# power.net
KiCad netlist of a schematic drawn in Altium Designer
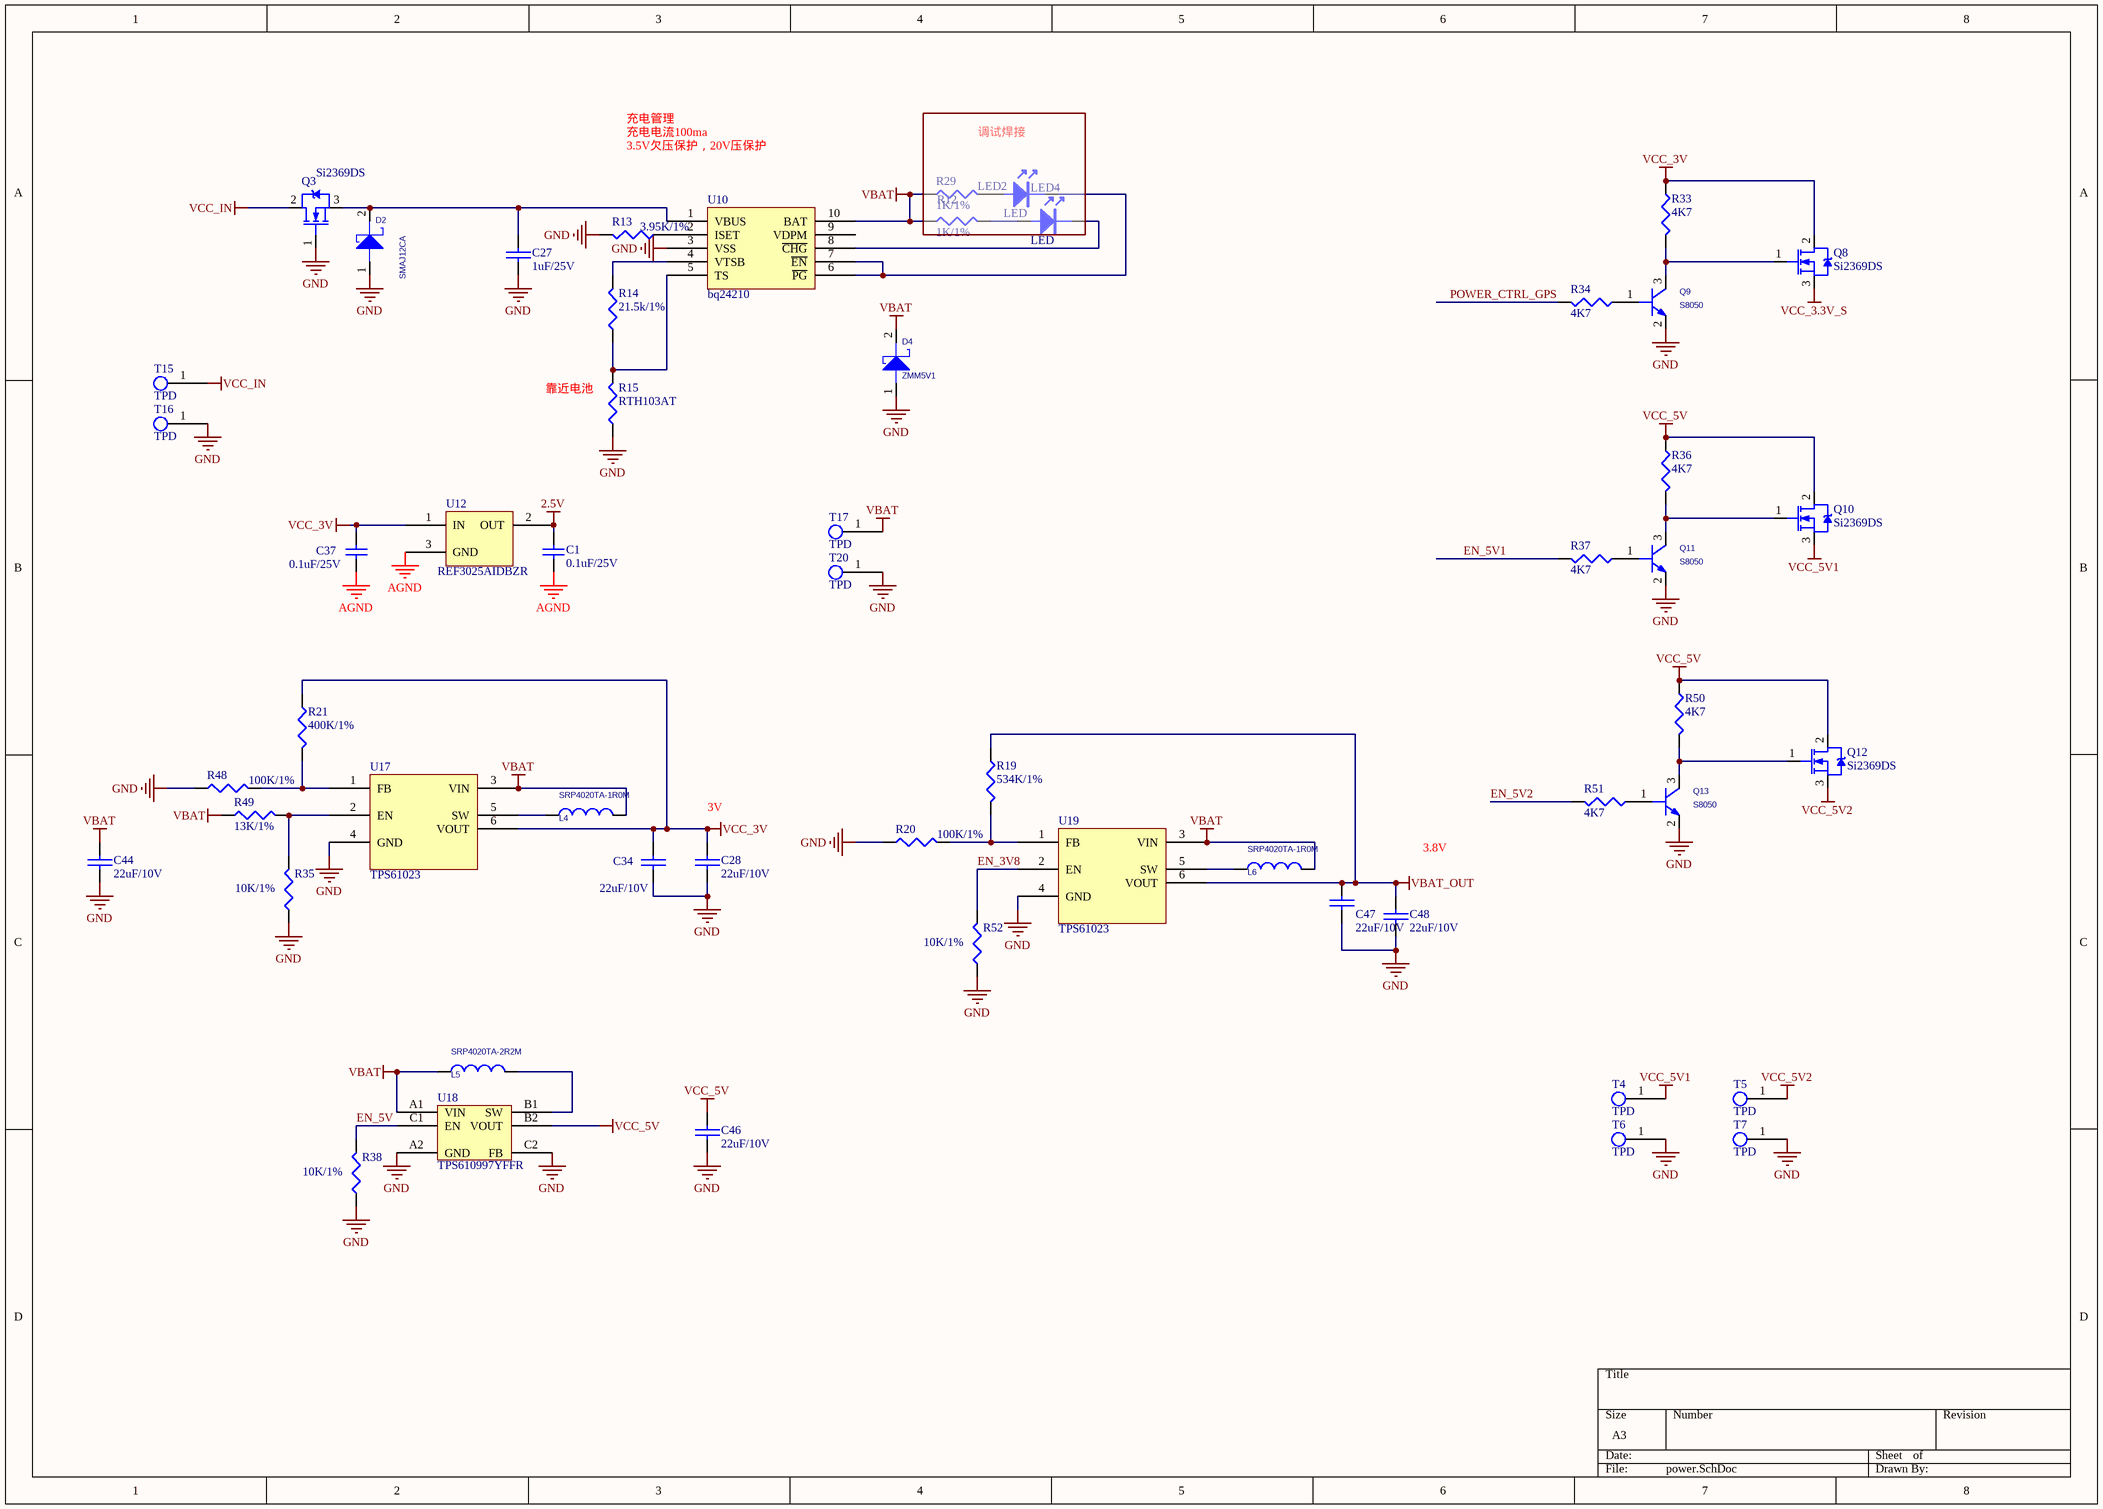
[diagram p0: power.SchDoc]

(export (version "E")
  (design (tool "Eeschema 10.0.6"))
  (components
    (comp (ref "C1")
      (value "0.1uF/25V")
      (footprint "0402c")
      (description "Capacitor")
      (fields (field (name "PUBLISHER") "Altium Limited"))
      (libsource (lib "Miscellaneous Devices") (part "Cap"))
    )
    (comp (ref "C27")
      (value "1uF/25V")
      (footprint "0402C")
      (description "Capacitor")
      (libsource (lib "ZWLIntegrated_Library") (part "CAP"))
    )
    (comp (ref "C28")
      (value "22uF/10V")
      (footprint "0805C")
      (description "Capacitor")
      (libsource (lib "ZWLIntegrated_Library") (part "CAP"))
    )
    (comp (ref "C34")
      (value "22uF/10V")
      (footprint "0805C")
      (description "Capacitor")
      (libsource (lib "ZWLIntegrated_Library") (part "CAP"))
    )
    (comp (ref "C37")
      (value "0.1uF/25V")
      (footprint "0402c")
      (description "Capacitor")
      (fields (field (name "PUBLISHER") "Altium Limited"))
      (libsource (lib "Miscellaneous Devices") (part "Cap"))
    )
    (comp (ref "C44")
      (value "22uF/10V")
      (footprint "0805C")
      (description "Capacitor")
      (libsource (lib "ZWLIntegrated_Library") (part "CAP"))
    )
    (comp (ref "C46")
      (value "22uF/10V")
      (footprint "0805C")
      (description "Capacitor")
      (libsource (lib "ZWLIntegrated_Library") (part "CAP"))
    )
    (comp (ref "C47")
      (value "22uF/10V")
      (footprint "0805C")
      (description "Capacitor")
      (libsource (lib "ZWLIntegrated_Library") (part "CAP"))
    )
    (comp (ref "C48")
      (value "22uF/10V")
      (footprint "0805C")
      (description "Capacitor")
      (libsource (lib "ZWLIntegrated_Library") (part "CAP"))
    )
    (comp (ref "D2")
      (value "SMAJ12CA")
      (footprint "SMA")
      (libsource (lib "KT_iBeacon") (part "DIODE_SCHOTTKY_0"))
    )
    (comp (ref "D4")
      (value "ZMM5V1")
      (footprint "LL-34(D1206)")
      (fields (field (name "Comment") "DIODE_SCHOTTKY_0"))
      (libsource (lib "KT_iBeacon") (part "DIODE_SCHOTTKY_0"))
    )
    (comp (ref "L4") (value "SRP4020TA-1R0M") (footprint "L2520") (libsource (lib "*") (part "INDUCTOR_1")))
    (comp (ref "L5") (value "SRP4020TA-2R2M") (footprint "L2520") (libsource (lib "*") (part "INDUCTOR_1")))
    (comp (ref "L6") (value "SRP4020TA-1R0M") (footprint "L2520") (libsource (lib "*") (part "INDUCTOR_1")))
    (comp (ref "LED2") (value "LED") (footprint "0603LED") (libsource (lib "我的元件库") (part "LED")))
    (comp (ref "LED4") (value "LED") (footprint "0603LED") (libsource (lib "我的元件库") (part "LED")))
    (comp (ref "Q3")
      (value "Si2369DS")
      (footprint "sot23-3")
      (description "NMOSFET")
      (libsource (lib "SM") (part "NCE4060K"))
    )
    (comp (ref "Q8")
      (value "Si2369DS")
      (footprint "sot23-3")
      (description "NMOSFET")
      (libsource (lib "SM") (part "NCE4060K"))
    )
    (comp (ref "Q9") (value "S8050") (footprint "SOT23-3") (libsource (lib "*") (part "2N1069_1")))
    (comp (ref "Q10")
      (value "Si2369DS")
      (footprint "sot23-3")
      (description "NMOSFET")
      (libsource (lib "SM") (part "NCE4060K"))
    )
    (comp (ref "Q11") (value "S8050") (footprint "SOT23-3") (libsource (lib "*") (part "2N1069_1")))
    (comp (ref "Q12")
      (value "Si2369DS")
      (footprint "sot23-3")
      (description "NMOSFET")
      (libsource (lib "SM") (part "NCE4060K"))
    )
    (comp (ref "Q13") (value "S8050") (footprint "SOT23-3") (libsource (lib "*") (part "2N1069_1")))
    (comp (ref "R12")
      (value "1K/1%")
      (footprint "0402R")
      (libsource (lib "ZWLIntegrated_Library") (part "RES1"))
    )
    (comp (ref "R13")
      (value "3.95K/1%")
      (footprint "0402R")
      (libsource (lib "ZWLIntegrated_Library") (part "RES1"))
    )
    (comp (ref "R14")
      (value "21.5k/1%")
      (footprint "0402R")
      (libsource (lib "ZWLIntegrated_Library") (part "RES1"))
    )
    (comp (ref "R15")
      (value "RTH103AT")
      (footprint "0603R")
      (libsource (lib "ZWLIntegrated_Library") (part "RES1"))
    )
    (comp (ref "R19")
      (value "534K/1%")
      (footprint "0402R")
      (libsource (lib "ZWLIntegrated_Library") (part "RES1"))
    )
    (comp (ref "R20")
      (value "100K/1%")
      (footprint "0402R")
      (libsource (lib "ZWLIntegrated_Library") (part "RES1"))
    )
    (comp (ref "R21")
      (value "400K/1%")
      (footprint "0402R")
      (libsource (lib "ZWLIntegrated_Library") (part "RES1"))
    )
    (comp (ref "R29")
      (value "1K/1%")
      (footprint "0402R")
      (libsource (lib "ZWLIntegrated_Library") (part "RES1"))
    )
    (comp (ref "R33")
      (value "4K7")
      (footprint "0402R")
      (libsource (lib "ZWLIntegrated_Library") (part "RES1"))
    )
    (comp (ref "R34")
      (value "4K7")
      (footprint "0402R")
      (libsource (lib "ZWLIntegrated_Library") (part "RES1"))
    )
    (comp (ref "R35")
      (value "10K/1%")
      (footprint "0402R")
      (libsource (lib "ZWLIntegrated_Library") (part "RES1"))
    )
    (comp (ref "R36")
      (value "4K7")
      (footprint "0402R")
      (libsource (lib "ZWLIntegrated_Library") (part "RES1"))
    )
    (comp (ref "R37")
      (value "4K7")
      (footprint "0402R")
      (libsource (lib "ZWLIntegrated_Library") (part "RES1"))
    )
    (comp (ref "R38")
      (value "10K/1%")
      (footprint "0402R")
      (libsource (lib "ZWLIntegrated_Library") (part "RES1"))
    )
    (comp (ref "R48")
      (value "100K/1%")
      (footprint "0402R")
      (libsource (lib "ZWLIntegrated_Library") (part "RES1"))
    )
    (comp (ref "R49")
      (value "13K/1%")
      (footprint "0402R")
      (libsource (lib "ZWLIntegrated_Library") (part "RES1"))
    )
    (comp (ref "R50")
      (value "4K7")
      (footprint "0402R")
      (libsource (lib "ZWLIntegrated_Library") (part "RES1"))
    )
    (comp (ref "R51")
      (value "4K7")
      (footprint "0402R")
      (libsource (lib "ZWLIntegrated_Library") (part "RES1"))
    )
    (comp (ref "R52")
      (value "10K/1%")
      (footprint "0402R")
      (libsource (lib "ZWLIntegrated_Library") (part "RES1"))
    )
    (comp (ref "T4") (value "TPD") (footprint "Pcblib_20110825:TP") (libsource (lib "stm32") (part "TPD")))
    (comp (ref "T5") (value "TPD") (footprint "Pcblib_20110825:TP") (libsource (lib "stm32") (part "TPD")))
    (comp (ref "T6") (value "TPD") (footprint "Pcblib_20110825:TP") (libsource (lib "stm32") (part "TPD")))
    (comp (ref "T7") (value "TPD") (footprint "Pcblib_20110825:TP") (libsource (lib "stm32") (part "TPD")))
    (comp (ref "T15") (value "TPD") (footprint "Pcblib_20110825:TP") (libsource (lib "stm32") (part "TPD")))
    (comp (ref "T16") (value "TPD") (footprint "Pcblib_20110825:TP") (libsource (lib "stm32") (part "TPD")))
    (comp (ref "T17") (value "TPD") (footprint "Pcblib_20110825:TP") (libsource (lib "stm32") (part "TPD")))
    (comp (ref "T20") (value "TPD") (footprint "Pcblib_20110825:TP") (libsource (lib "stm32") (part "TPD")))
    (comp (ref "U10")
      (value "bq24210")
      (footprint "QFN50P200X300X80-10N")
      (libsource (lib "stm32") (part "bq2410"))
    )
    (comp (ref "U12")
      (value "REF3025AIDBZR")
      (footprint "SOT23-3")
      (libsource (lib "Schlib1") (part "REF3012"))
    )
    (comp (ref "U17") (value "TPS61023") (footprint "SOT563-6") (libsource (lib "stm32") (part "TPS61023")))
    (comp (ref "U18")
      (value "TPS610997YFFR")
      (footprint "TPS610997YFFR")
      (libsource (lib "stm32") (part "TPS610997YFFR"))
    )
    (comp (ref "U19") (value "TPS61023") (footprint "SOT563-6") (libsource (lib "stm32") (part "TPS61023")))
  )
  (nets
    (net (code "1") (name "/EN_3V8") (class "Default")
      (node (ref "R52") (pin "2") (pinfunction "2_2") (pintype "passive"))
      (node (ref "U19") (pin "2") (pinfunction "EN_2") (pintype "passive"))
    )
    (net (code "2") (name "/EN_5V") (class "Default")
      (node (ref "R38") (pin "2") (pinfunction "2_2") (pintype "passive"))
      (node (ref "U18") (pin "C1") (pinfunction "EN_C1") (pintype "passive"))
    )
    (net (code "3") (name "/EN_5V1") (class "Default")
      (node (ref "R37") (pin "2") (pinfunction "2_2") (pintype "passive"))
    )
    (net (code "4") (name "/EN_5V2") (class "Default")
      (node (ref "R51") (pin "2") (pinfunction "2_2") (pintype "passive"))
    )
    (net (code "5") (name "/POWER_CTRL_GPS") (class "Default")
      (node (ref "R34") (pin "2") (pinfunction "2_2") (pintype "passive"))
    )
    (net (code "6") (name "2.5V") (class "Default")
      (node (ref "C1") (pin "1") (pinfunction "1_1") (pintype "passive"))
      (node (ref "U12") (pin "2") (pinfunction "OUT_2") (pintype "passive"))
    )
    (net (code "7") (name "AGND") (class "Default")
      (node (ref "C1") (pin "2") (pinfunction "2_2") (pintype "passive"))
      (node (ref "C37") (pin "2") (pinfunction "2_2") (pintype "passive"))
      (node (ref "U12") (pin "3") (pinfunction "GND_3") (pintype "passive"))
    )
    (net (code "8") (name "GND") (class "Default")
      (node (ref "C27") (pin "2") (pinfunction "2_2") (pintype "passive"))
      (node (ref "C28") (pin "2") (pinfunction "2_2") (pintype "passive"))
      (node (ref "C34") (pin "2") (pinfunction "2_2") (pintype "passive"))
      (node (ref "C44") (pin "2") (pinfunction "2_2") (pintype "passive"))
      (node (ref "C46") (pin "2") (pinfunction "2_2") (pintype "passive"))
      (node (ref "C47") (pin "2") (pinfunction "2_2") (pintype "passive"))
      (node (ref "C48") (pin "2") (pinfunction "2_2") (pintype "passive"))
      (node (ref "D2") (pin "1") (pinfunction "1_1") (pintype "passive"))
      (node (ref "D4") (pin "1") (pinfunction "1_1") (pintype "passive"))
      (node (ref "Q11") (pin "2") (pinfunction "E_2") (pintype "passive"))
      (node (ref "Q13") (pin "2") (pinfunction "E_2") (pintype "passive"))
      (node (ref "Q3") (pin "1") (pinfunction "G_1") (pintype "passive"))
      (node (ref "Q9") (pin "2") (pinfunction "E_2") (pintype "passive"))
      (node (ref "R13") (pin "2") (pinfunction "2_2") (pintype "passive"))
      (node (ref "R15") (pin "1") (pinfunction "1_1") (pintype "passive"))
      (node (ref "R20") (pin "1") (pinfunction "1_1") (pintype "passive"))
      (node (ref "R35") (pin "1") (pinfunction "1_1") (pintype "passive"))
      (node (ref "R38") (pin "1") (pinfunction "1_1") (pintype "passive"))
      (node (ref "R48") (pin "1") (pinfunction "1_1") (pintype "passive"))
      (node (ref "R52") (pin "1") (pinfunction "1_1") (pintype "passive"))
      (node (ref "T16") (pin "1") (pintype "passive"))
      (node (ref "T20") (pin "1") (pintype "passive"))
      (node (ref "T6") (pin "1") (pintype "passive"))
      (node (ref "T7") (pin "1") (pintype "passive"))
      (node (ref "U10") (pin "3") (pinfunction "VSS_3") (pintype "passive"))
      (node (ref "U17") (pin "4") (pinfunction "GND_4") (pintype "passive"))
      (node (ref "U18") (pin "A2") (pinfunction "GND_A2") (pintype "passive"))
      (node (ref "U18") (pin "C2") (pinfunction "FB_C2") (pintype "passive"))
      (node (ref "U19") (pin "4") (pinfunction "GND_4") (pintype "passive"))
    )
    (net (code "9") (name "Net-(LED2-Pad1)") (class "Default")
      (node (ref "LED2") (pin "1") (pinfunction "1_1") (pintype "passive"))
      (node (ref "R29") (pin "2") (pinfunction "2_2") (pintype "passive"))
    )
    (net (code "10") (name "Net-(LED4-Pad1)") (class "Default")
      (node (ref "LED4") (pin "1") (pinfunction "1_1") (pintype "passive"))
      (node (ref "R12") (pin "2") (pinfunction "2_2") (pintype "passive"))
    )
    (net (code "11") (name "Net-(Q3-S)") (class "Default")
      (node (ref "C27") (pin "1") (pinfunction "1_1") (pintype "passive"))
      (node (ref "D2") (pin "2") (pinfunction "2_2") (pintype "passive"))
      (node (ref "Q3") (pin "3") (pinfunction "S_3") (pintype "passive"))
      (node (ref "U10") (pin "1") (pinfunction "VBUS_1") (pintype "passive"))
    )
    (net (code "12") (name "Net-(Q8-G)") (class "Default")
      (node (ref "Q8") (pin "1") (pinfunction "G_1") (pintype "passive"))
      (node (ref "Q9") (pin "3") (pinfunction "C_3") (pintype "passive"))
      (node (ref "R33") (pin "2") (pinfunction "2_2") (pintype "passive"))
    )
    (net (code "13") (name "Net-(Q9-B)") (class "Default")
      (node (ref "Q9") (pin "1") (pinfunction "B_1") (pintype "passive"))
      (node (ref "R34") (pin "1") (pinfunction "1_1") (pintype "passive"))
    )
    (net (code "14") (name "Net-(Q10-G)") (class "Default")
      (node (ref "Q10") (pin "1") (pinfunction "G_1") (pintype "passive"))
      (node (ref "Q11") (pin "3") (pinfunction "C_3") (pintype "passive"))
      (node (ref "R36") (pin "2") (pinfunction "2_2") (pintype "passive"))
    )
    (net (code "15") (name "Net-(Q11-B)") (class "Default")
      (node (ref "Q11") (pin "1") (pinfunction "B_1") (pintype "passive"))
      (node (ref "R37") (pin "1") (pinfunction "1_1") (pintype "passive"))
    )
    (net (code "16") (name "Net-(Q12-G)") (class "Default")
      (node (ref "Q12") (pin "1") (pinfunction "G_1") (pintype "passive"))
      (node (ref "Q13") (pin "3") (pinfunction "C_3") (pintype "passive"))
      (node (ref "R50") (pin "2") (pinfunction "2_2") (pintype "passive"))
    )
    (net (code "17") (name "Net-(Q13-B)") (class "Default")
      (node (ref "Q13") (pin "1") (pinfunction "B_1") (pintype "passive"))
      (node (ref "R51") (pin "1") (pinfunction "1_1") (pintype "passive"))
    )
    (net (code "18") (name "Net-(U10-ISET)") (class "Default")
      (node (ref "R13") (pin "1") (pinfunction "1_1") (pintype "passive"))
      (node (ref "U10") (pin "2") (pinfunction "ISET_2") (pintype "passive"))
    )
    (net (code "19") (name "Net-(U10-TS)") (class "Default")
      (node (ref "R14") (pin "1") (pinfunction "1_1") (pintype "passive"))
      (node (ref "R15") (pin "2") (pinfunction "2_2") (pintype "passive"))
      (node (ref "U10") (pin "5") (pinfunction "TS_5") (pintype "passive"))
    )
    (net (code "20") (name "Net-(U10-VTSB)") (class "Default")
      (node (ref "R14") (pin "2") (pinfunction "2_2") (pintype "passive"))
      (node (ref "U10") (pin "4") (pinfunction "VTSB_4") (pintype "passive"))
    )
    (net (code "21") (name "Net-(U10-~{CHG})") (class "Default")
      (node (ref "LED4") (pin "2") (pinfunction "2_2") (pintype "passive"))
      (node (ref "U10") (pin "8") (pinfunction "~{CHG}_8") (pintype "passive"))
    )
    (net (code "22") (name "Net-(U10-~{EN})") (class "Default")
      (node (ref "LED2") (pin "2") (pinfunction "2_2") (pintype "passive"))
      (node (ref "U10") (pin "6") (pinfunction "~{PG}_6") (pintype "passive"))
      (node (ref "U10") (pin "7") (pinfunction "~{EN}_7") (pintype "passive"))
    )
    (net (code "23") (name "Net-(U17-EN)") (class "Default")
      (node (ref "R35") (pin "2") (pinfunction "2_2") (pintype "passive"))
      (node (ref "R49") (pin "2") (pinfunction "2_2") (pintype "passive"))
      (node (ref "U17") (pin "2") (pinfunction "EN_2") (pintype "passive"))
    )
    (net (code "24") (name "Net-(U17-FB)") (class "Default")
      (node (ref "R21") (pin "2") (pinfunction "2_2") (pintype "passive"))
      (node (ref "R48") (pin "2") (pinfunction "2_2") (pintype "passive"))
      (node (ref "U17") (pin "1") (pinfunction "FB_1") (pintype "passive"))
    )
    (net (code "25") (name "Net-(U17-SW)") (class "Default")
      (node (ref "L4") (pin "1") (pinfunction "1_1") (pintype "passive"))
      (node (ref "U17") (pin "5") (pinfunction "SW_5") (pintype "passive"))
    )
    (net (code "26") (name "Net-(U18-SW)") (class "Default")
      (node (ref "L5") (pin "2") (pinfunction "2_2") (pintype "passive"))
      (node (ref "U18") (pin "B1") (pinfunction "SW_B1") (pintype "passive"))
    )
    (net (code "27") (name "Net-(U19-FB)") (class "Default")
      (node (ref "R19") (pin "2") (pinfunction "2_2") (pintype "passive"))
      (node (ref "R20") (pin "2") (pinfunction "2_2") (pintype "passive"))
      (node (ref "U19") (pin "1") (pinfunction "FB_1") (pintype "passive"))
    )
    (net (code "28") (name "Net-(U19-SW)") (class "Default")
      (node (ref "L6") (pin "1") (pinfunction "1_1") (pintype "passive"))
      (node (ref "U19") (pin "5") (pinfunction "SW_5") (pintype "passive"))
    )
    (net (code "29") (name "VBAT") (class "Default")
      (node (ref "C44") (pin "1") (pinfunction "1_1") (pintype "passive"))
      (node (ref "D4") (pin "2") (pinfunction "2_2") (pintype "passive"))
      (node (ref "L4") (pin "2") (pinfunction "2_2") (pintype "passive"))
      (node (ref "L5") (pin "1") (pinfunction "1_1") (pintype "passive"))
      (node (ref "L6") (pin "2") (pinfunction "2_2") (pintype "passive"))
      (node (ref "R12") (pin "1") (pinfunction "1_1") (pintype "passive"))
      (node (ref "R29") (pin "1") (pinfunction "1_1") (pintype "passive"))
      (node (ref "R49") (pin "1") (pinfunction "1_1") (pintype "passive"))
      (node (ref "T17") (pin "1") (pintype "passive"))
      (node (ref "U10") (pin "10") (pinfunction "BAT_10") (pintype "passive"))
      (node (ref "U17") (pin "3") (pinfunction "VIN_3") (pintype "passive"))
      (node (ref "U18") (pin "A1") (pinfunction "VIN_A1") (pintype "passive"))
      (node (ref "U19") (pin "3") (pinfunction "VIN_3") (pintype "passive"))
    )
    (net (code "30") (name "VBAT_OUT") (class "Default")
      (node (ref "C47") (pin "1") (pinfunction "1_1") (pintype "passive"))
      (node (ref "C48") (pin "1") (pinfunction "1_1") (pintype "passive"))
      (node (ref "R19") (pin "1") (pinfunction "1_1") (pintype "passive"))
      (node (ref "U19") (pin "6") (pinfunction "VOUT_6") (pintype "passive"))
    )
    (net (code "31") (name "VCC_3.3V_S") (class "Default")
      (node (ref "Q8") (pin "3") (pinfunction "S_3") (pintype "passive"))
    )
    (net (code "32") (name "VCC_3V") (class "Default")
      (node (ref "C28") (pin "1") (pinfunction "1_1") (pintype "passive"))
      (node (ref "C34") (pin "1") (pinfunction "1_1") (pintype "passive"))
      (node (ref "C37") (pin "1") (pinfunction "1_1") (pintype "passive"))
      (node (ref "Q8") (pin "2") (pinfunction "D_2") (pintype "passive"))
      (node (ref "R21") (pin "1") (pinfunction "1_1") (pintype "passive"))
      (node (ref "R33") (pin "1") (pinfunction "1_1") (pintype "passive"))
      (node (ref "U12") (pin "1") (pinfunction "IN_1") (pintype "passive"))
      (node (ref "U17") (pin "6") (pinfunction "VOUT_6") (pintype "passive"))
    )
    (net (code "33") (name "VCC_5V") (class "Default")
      (node (ref "C46") (pin "1") (pinfunction "1_1") (pintype "passive"))
      (node (ref "Q10") (pin "2") (pinfunction "D_2") (pintype "passive"))
      (node (ref "Q12") (pin "2") (pinfunction "D_2") (pintype "passive"))
      (node (ref "R36") (pin "1") (pinfunction "1_1") (pintype "passive"))
      (node (ref "R50") (pin "1") (pinfunction "1_1") (pintype "passive"))
      (node (ref "U18") (pin "B2") (pinfunction "VOUT_B2") (pintype "passive"))
    )
    (net (code "34") (name "VCC_5V1") (class "Default")
      (node (ref "Q10") (pin "3") (pinfunction "S_3") (pintype "passive"))
      (node (ref "T4") (pin "1") (pintype "passive"))
    )
    (net (code "35") (name "VCC_5V2") (class "Default")
      (node (ref "Q12") (pin "3") (pinfunction "S_3") (pintype "passive"))
      (node (ref "T5") (pin "1") (pintype "passive"))
    )
    (net (code "36") (name "VCC_IN") (class "Default")
      (node (ref "Q3") (pin "2") (pinfunction "D_2") (pintype "passive"))
      (node (ref "T15") (pin "1") (pintype "passive"))
    )
    (net (code "37") (name "unconnected-(U10-VDPM-Pad9)") (class "Default")
      (node (ref "U10") (pin "9") (pinfunction "VDPM_9") (pintype "passive"))
    )
  )
)
